# Driver.net
KiCad netlist of a schematic drawn in Altium Designer
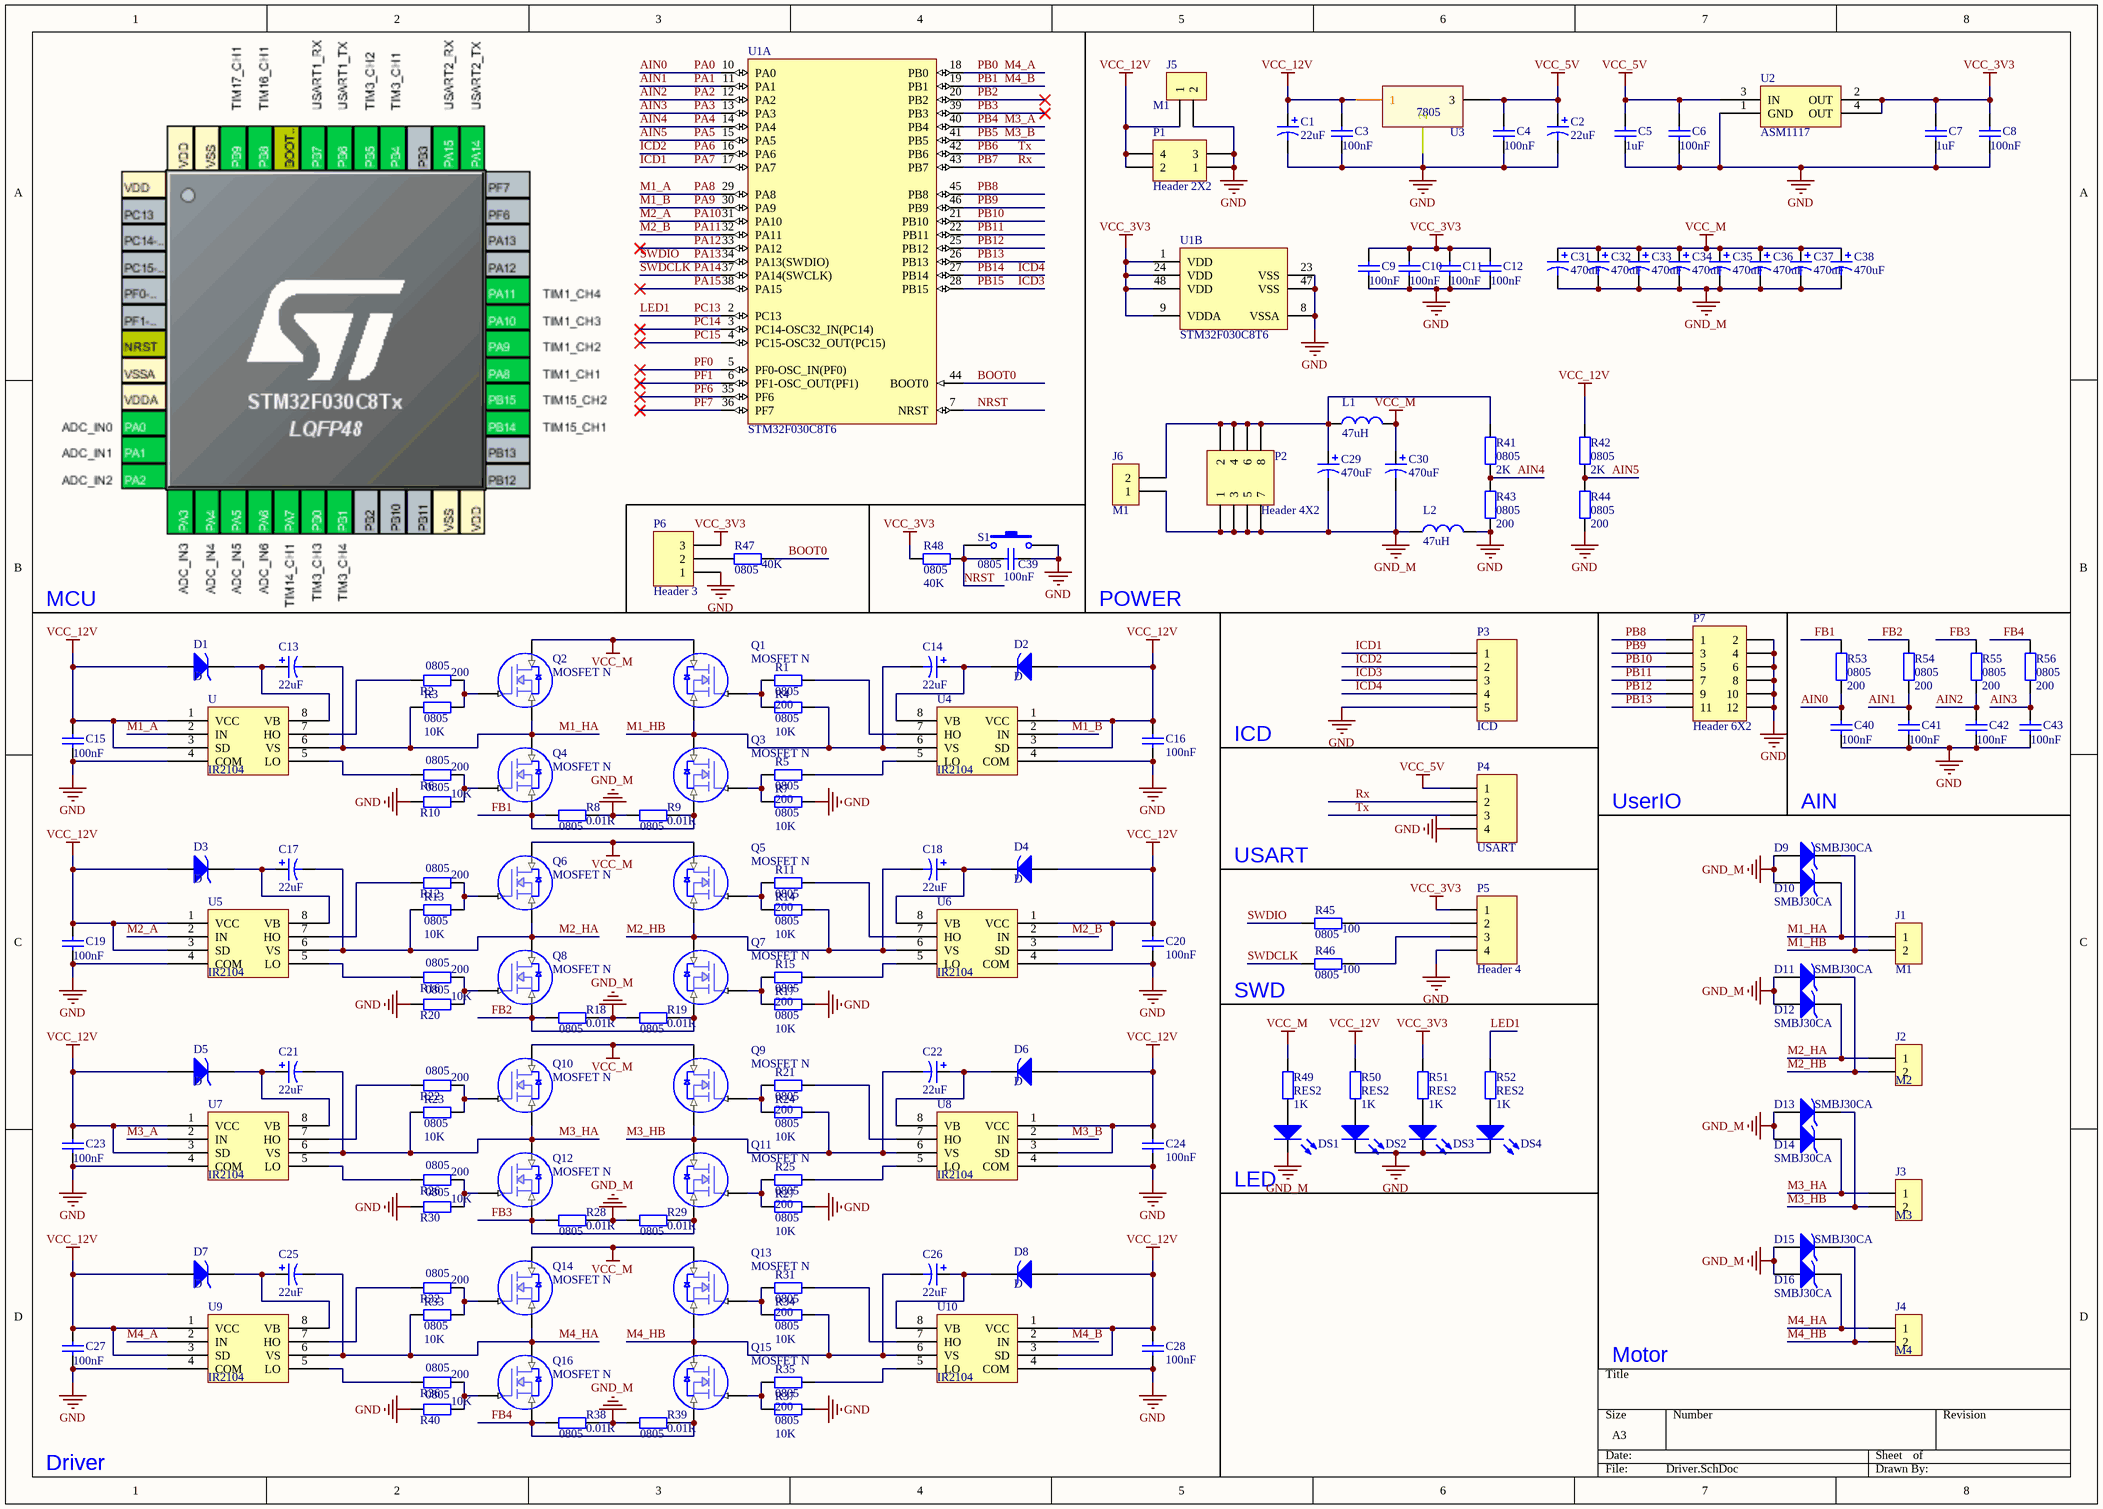
[diagram p0: Driver.SchDoc]

(export (version "E")
  (design (tool "Eeschema 10.0.6"))
  (components
    (comp (ref "C1")
      (value "22uF")
      (footprint "CD C(6032)")
      (fields (field (name "Comment") "CAP-ELEC"))
      (libsource (lib "QT") (part "CAP-ELEC"))
    )
    (comp (ref "C2")
      (value "22uF")
      (footprint "CD C(6032)")
      (fields (field (name "Comment") "CAP-ELEC"))
      (libsource (lib "QT") (part "CAP-ELEC"))
    )
    (comp (ref "C3")
      (value "100nF")
      (footprint "C 0805_L")
      (fields (field (name "Comment") "CAP"))
      (libsource (lib "QT") (part "CAP"))
    )
    (comp (ref "C4")
      (value "100nF")
      (footprint "C 0805_L")
      (fields (field (name "Comment") "CAP"))
      (libsource (lib "QT") (part "CAP"))
    )
    (comp (ref "C5")
      (value "1uF")
      (footprint "C 0805_L")
      (fields (field (name "Comment") "CAP"))
      (libsource (lib "QT") (part "CAP"))
    )
    (comp (ref "C6")
      (value "100nF")
      (footprint "C 0805_L")
      (fields (field (name "Comment") "CAP"))
      (libsource (lib "QT") (part "CAP"))
    )
    (comp (ref "C7")
      (value "1uF")
      (footprint "C 0805_L")
      (fields (field (name "Comment") "CAP"))
      (libsource (lib "QT") (part "CAP"))
    )
    (comp (ref "C8")
      (value "100nF")
      (footprint "C 0805_L")
      (fields (field (name "Comment") "CAP"))
      (libsource (lib "QT") (part "CAP"))
    )
    (comp (ref "C9")
      (value "100nF")
      (footprint "C 0805_L")
      (fields (field (name "Comment") "CAP"))
      (libsource (lib "QT") (part "CAP"))
    )
    (comp (ref "C10")
      (value "100nF")
      (footprint "C 0805_L")
      (fields (field (name "Comment") "CAP"))
      (libsource (lib "QT") (part "CAP"))
    )
    (comp (ref "C11")
      (value "100nF")
      (footprint "C 0805_L")
      (fields (field (name "Comment") "CAP"))
      (libsource (lib "QT") (part "CAP"))
    )
    (comp (ref "C12")
      (value "100nF")
      (footprint "C 0805_L")
      (fields (field (name "Comment") "CAP"))
      (libsource (lib "QT") (part "CAP"))
    )
    (comp (ref "C13")
      (value "22uF")
      (footprint "CD C(6032)")
      (fields (field (name "Comment") "CAP-ELEC"))
      (libsource (lib "QT") (part "CAP-ELEC"))
    )
    (comp (ref "C14")
      (value "22uF")
      (footprint "CD C(6032)")
      (fields (field (name "Comment") "CAP-ELEC"))
      (libsource (lib "") (part "CAP-ELEC_1"))
    )
    (comp (ref "C15")
      (value "100nF")
      (footprint "C 0805_L")
      (fields (field (name "Comment") "CAP"))
      (libsource (lib "QT") (part "CAP"))
    )
    (comp (ref "C16")
      (value "100nF")
      (footprint "C 0805_L")
      (fields (field (name "Comment") "CAP"))
      (libsource (lib "QT") (part "CAP"))
    )
    (comp (ref "C17")
      (value "22uF")
      (footprint "CD C(6032)")
      (fields (field (name "Comment") "CAP-ELEC"))
      (libsource (lib "QT") (part "CAP-ELEC"))
    )
    (comp (ref "C18")
      (value "22uF")
      (footprint "CD C(6032)")
      (fields (field (name "Comment") "CAP-ELEC"))
      (libsource (lib "") (part "CAP-ELEC_1"))
    )
    (comp (ref "C19")
      (value "100nF")
      (footprint "C 0805_L")
      (fields (field (name "Comment") "CAP"))
      (libsource (lib "QT") (part "CAP"))
    )
    (comp (ref "C20")
      (value "100nF")
      (footprint "C 0805_L")
      (fields (field (name "Comment") "CAP"))
      (libsource (lib "QT") (part "CAP"))
    )
    (comp (ref "C21")
      (value "22uF")
      (footprint "CD C(6032)")
      (fields (field (name "Comment") "CAP-ELEC"))
      (libsource (lib "QT") (part "CAP-ELEC"))
    )
    (comp (ref "C22")
      (value "22uF")
      (footprint "CD C(6032)")
      (fields (field (name "Comment") "CAP-ELEC"))
      (libsource (lib "") (part "CAP-ELEC_1"))
    )
    (comp (ref "C23")
      (value "100nF")
      (footprint "C 0805_L")
      (fields (field (name "Comment") "CAP"))
      (libsource (lib "QT") (part "CAP"))
    )
    (comp (ref "C24")
      (value "100nF")
      (footprint "C 0805_L")
      (fields (field (name "Comment") "CAP"))
      (libsource (lib "QT") (part "CAP"))
    )
    (comp (ref "C25")
      (value "22uF")
      (footprint "CD C(6032)")
      (fields (field (name "Comment") "CAP-ELEC"))
      (libsource (lib "QT") (part "CAP-ELEC"))
    )
    (comp (ref "C26")
      (value "22uF")
      (footprint "CD C(6032)")
      (fields (field (name "Comment") "CAP-ELEC"))
      (libsource (lib "") (part "CAP-ELEC_1"))
    )
    (comp (ref "C27")
      (value "100nF")
      (footprint "C 0805_L")
      (fields (field (name "Comment") "CAP"))
      (libsource (lib "QT") (part "CAP"))
    )
    (comp (ref "C28")
      (value "100nF")
      (footprint "C 0805_L")
      (fields (field (name "Comment") "CAP"))
      (libsource (lib "QT") (part "CAP"))
    )
    (comp (ref "C29")
      (value "470uF")
      (footprint "CM E(8*10.2)")
      (fields (field (name "Comment") "CAP-ELEC"))
      (libsource (lib "QT") (part "CAP-ELEC"))
    )
    (comp (ref "C30")
      (value "470uF")
      (footprint "CM E(8*10.2)")
      (fields (field (name "Comment") "CAP-ELEC"))
      (libsource (lib "QT") (part "CAP-ELEC"))
    )
    (comp (ref "C31")
      (value "470uF")
      (footprint "CM E(8*10.2)")
      (fields (field (name "Comment") "CAP-ELEC"))
      (libsource (lib "QT") (part "CAP-ELEC"))
    )
    (comp (ref "C32")
      (value "470uF")
      (footprint "CM E(8*10.2)")
      (fields (field (name "Comment") "CAP-ELEC"))
      (libsource (lib "QT") (part "CAP-ELEC"))
    )
    (comp (ref "C33")
      (value "470uF")
      (footprint "CM E(8*10.2)")
      (fields (field (name "Comment") "CAP-ELEC"))
      (libsource (lib "QT") (part "CAP-ELEC"))
    )
    (comp (ref "C34")
      (value "470uF")
      (footprint "CM E(8*10.2)")
      (fields (field (name "Comment") "CAP-ELEC"))
      (libsource (lib "QT") (part "CAP-ELEC"))
    )
    (comp (ref "C35")
      (value "470uF")
      (footprint "CM E(8*10.2)")
      (fields (field (name "Comment") "CAP-ELEC"))
      (libsource (lib "QT") (part "CAP-ELEC"))
    )
    (comp (ref "C36")
      (value "470uF")
      (footprint "CM E(8*10.2)")
      (fields (field (name "Comment") "CAP-ELEC"))
      (libsource (lib "QT") (part "CAP-ELEC"))
    )
    (comp (ref "C37")
      (value "470uF")
      (footprint "CM E(8*10.2)")
      (fields (field (name "Comment") "CAP-ELEC"))
      (libsource (lib "QT") (part "CAP-ELEC"))
    )
    (comp (ref "C38")
      (value "470uF")
      (footprint "CM E(8*10.2)")
      (fields (field (name "Comment") "CAP-ELEC"))
      (libsource (lib "QT") (part "CAP-ELEC"))
    )
    (comp (ref "C39")
      (value "0805")
      (footprint "C 0805_M")
      (fields (field (name "ALTIUM_VALUE") "100nF"))
      (libsource (lib "QT") (part "CAP"))
    )
    (comp (ref "C40")
      (value "100nF")
      (footprint "C 0805_L")
      (fields (field (name "Comment") "CAP"))
      (libsource (lib "QT") (part "CAP"))
    )
    (comp (ref "C41")
      (value "100nF")
      (footprint "C 0805_L")
      (fields (field (name "Comment") "CAP"))
      (libsource (lib "QT") (part "CAP"))
    )
    (comp (ref "C42")
      (value "100nF")
      (footprint "C 0805_L")
      (fields (field (name "Comment") "CAP"))
      (libsource (lib "QT") (part "CAP"))
    )
    (comp (ref "C43")
      (value "100nF")
      (footprint "C 0805_L")
      (fields (field (name "Comment") "CAP"))
      (libsource (lib "QT") (part "CAP"))
    )
    (comp (ref "D1")
      (value "D")
      (footprint "SOD-123")
      (description "High Conductance Fast Diode")
      (fields (field (name "PUBLISHER") "Altium Limited"))
      (libsource (lib "QT") (part "D"))
    )
    (comp (ref "D2")
      (value "D")
      (footprint "SOD-123")
      (description "High Conductance Fast Diode")
      (fields (field (name "PUBLISHER") "Altium Limited"))
      (libsource (lib "QT") (part "D"))
    )
    (comp (ref "D3")
      (value "D")
      (footprint "SOD-123")
      (description "High Conductance Fast Diode")
      (fields (field (name "PUBLISHER") "Altium Limited"))
      (libsource (lib "QT") (part "D"))
    )
    (comp (ref "D4")
      (value "D")
      (footprint "SOD-123")
      (description "High Conductance Fast Diode")
      (fields (field (name "PUBLISHER") "Altium Limited"))
      (libsource (lib "QT") (part "D"))
    )
    (comp (ref "D5")
      (value "D")
      (footprint "SOD-123")
      (description "High Conductance Fast Diode")
      (fields (field (name "PUBLISHER") "Altium Limited"))
      (libsource (lib "QT") (part "D"))
    )
    (comp (ref "D6")
      (value "D")
      (footprint "SOD-123")
      (description "High Conductance Fast Diode")
      (fields (field (name "PUBLISHER") "Altium Limited"))
      (libsource (lib "QT") (part "D"))
    )
    (comp (ref "D7")
      (value "D")
      (footprint "SOD-123")
      (description "High Conductance Fast Diode")
      (fields (field (name "PUBLISHER") "Altium Limited"))
      (libsource (lib "QT") (part "D"))
    )
    (comp (ref "D8")
      (value "D")
      (footprint "SOD-123")
      (description "High Conductance Fast Diode")
      (fields (field (name "PUBLISHER") "Altium Limited"))
      (libsource (lib "QT") (part "D"))
    )
    (comp (ref "D9")
      (value "SMBJ30CA")
      (footprint "SMB")
      (description "High Conductance Fast Diode")
      (fields (field (name "PUBLISHER") "Altium Limited"))
      (libsource (lib "QT") (part "D"))
    )
    (comp (ref "D10")
      (value "SMBJ30CA")
      (footprint "SMB")
      (description "High Conductance Fast Diode")
      (fields (field (name "PUBLISHER") "Altium Limited"))
      (libsource (lib "QT") (part "D"))
    )
    (comp (ref "D11")
      (value "SMBJ30CA")
      (footprint "SMB")
      (description "High Conductance Fast Diode")
      (fields (field (name "PUBLISHER") "Altium Limited"))
      (libsource (lib "QT") (part "D"))
    )
    (comp (ref "D12")
      (value "SMBJ30CA")
      (footprint "SMB")
      (description "High Conductance Fast Diode")
      (fields (field (name "PUBLISHER") "Altium Limited"))
      (libsource (lib "QT") (part "D"))
    )
    (comp (ref "D13")
      (value "SMBJ30CA")
      (footprint "SMB")
      (description "High Conductance Fast Diode")
      (fields (field (name "PUBLISHER") "Altium Limited"))
      (libsource (lib "QT") (part "D"))
    )
    (comp (ref "D14")
      (value "SMBJ30CA")
      (footprint "SMB")
      (description "High Conductance Fast Diode")
      (fields (field (name "PUBLISHER") "Altium Limited"))
      (libsource (lib "QT") (part "D"))
    )
    (comp (ref "D15")
      (value "SMBJ30CA")
      (footprint "SMB")
      (description "High Conductance Fast Diode")
      (fields (field (name "PUBLISHER") "Altium Limited"))
      (libsource (lib "QT") (part "D"))
    )
    (comp (ref "D16")
      (value "SMBJ30CA")
      (footprint "SMB")
      (description "High Conductance Fast Diode")
      (fields (field (name "PUBLISHER") "Altium Limited"))
      (libsource (lib "QT") (part "D"))
    )
    (comp (ref "DS1") (value "LED") (footprint "LED 0805B") (libsource (lib "QT") (part "LED")))
    (comp (ref "DS2") (value "LED") (footprint "LED 0805B") (libsource (lib "QT") (part "LED")))
    (comp (ref "DS3") (value "LED") (footprint "LED 0805B") (libsource (lib "QT") (part "LED")))
    (comp (ref "DS4") (value "LED") (footprint "LED 0805B") (libsource (lib "QT") (part "LED")))
    (comp (ref "J1") (value "M1") (footprint "DG1282-5.0") (libsource (lib "") (part "CON2_1")))
    (comp (ref "J2") (value "M2") (footprint "DG1282-5.0") (libsource (lib "") (part "CON2_1")))
    (comp (ref "J3") (value "M3") (footprint "DG1282-5.0") (libsource (lib "") (part "CON2_1")))
    (comp (ref "J4") (value "M4") (footprint "DG1282-5.0") (libsource (lib "") (part "CON2_1")))
    (comp (ref "J5") (value "M1") (footprint "DG1282-5.0") (libsource (lib "常用元件库") (part "CON2")))
    (comp (ref "J6") (value "M1") (footprint "DG1282-5.0") (libsource (lib "") (part "CON2_2")))
    (comp (ref "L1")
      (value "47uH")
      (footprint "L-SMD-12")
      (description "电感")
      (fields (field (name "Comment") "Inductor") (field (name "PUBLISHER") "Altium Limited"))
      (libsource (lib "Fszhang") (part "Inductor"))
    )
    (comp (ref "L2")
      (value "47uH")
      (footprint "L-SMD-12")
      (description "电感")
      (fields (field (name "Comment") "Inductor") (field (name "PUBLISHER") "Altium Limited"))
      (libsource (lib "Fszhang") (part "Inductor"))
    )
    (comp (ref "P1")
      (value "Header 2X2")
      (footprint "HDR2.54-LI-2x2P")
      (description "Header, 2-Pin, Dual row")
      (fields (field (name "PUBLISHER") "Altium Limited"))
      (libsource (lib "QT") (part "Header 2X2"))
    )
    (comp (ref "P2")
      (value "Header 4X2")
      (footprint "HDR2.54-LI-2x4P")
      (description "Header, 4-Pin, Dual row")
      (fields (field (name "PUBLISHER") "Altium Limited"))
      (libsource (lib "QT") (part "Header 4X2"))
    )
    (comp (ref "P3")
      (value "ICD")
      (footprint "HDR2.54-LI-5P")
      (description "Header, 5-Pin")
      (fields (field (name "PUBLISHER") "Altium Limited"))
      (libsource (lib "QT") (part "Header 5"))
    )
    (comp (ref "P4")
      (value "USART")
      (footprint "HDR2.54-LI-4P")
      (description "Header, 4-Pin")
      (fields (field (name "PUBLISHER") "Altium Limited"))
      (libsource (lib "QT") (part "Header 4"))
    )
    (comp (ref "P5")
      (value "Header 4")
      (footprint "HDR2.54-LI-4P")
      (description "Header, 4-Pin")
      (fields (field (name "PUBLISHER") "Altium Limited"))
      (libsource (lib "QT") (part "Header 4"))
    )
    (comp (ref "P6")
      (value "Header 3")
      (footprint "HDR2.54-LI-3P")
      (description "Header, 3-Pin")
      (fields (field (name "PUBLISHER") "Altium Limited"))
      (libsource (lib "QT") (part "Header 3"))
    )
    (comp (ref "P7")
      (value "Header 6X2")
      (footprint "HDR2.54-LI-2x6P")
      (description "Header, 6-Pin, Dual row")
      (fields (field (name "PUBLISHER") "Altium Limited"))
      (libsource (lib "QT") (part "Header 6X2"))
    )
    (comp (ref "Q1") (value "MOSFET N") (footprint "TO252") (libsource (lib "场效应管及可控硅") (part "MOSFET N")))
    (comp (ref "Q2") (value "MOSFET N") (footprint "TO252") (libsource (lib "场效应管及可控硅") (part "MOSFET N")))
    (comp (ref "Q3") (value "MOSFET N") (footprint "TO252") (libsource (lib "场效应管及可控硅") (part "MOSFET N")))
    (comp (ref "Q4") (value "MOSFET N") (footprint "TO252") (libsource (lib "场效应管及可控硅") (part "MOSFET N")))
    (comp (ref "Q5") (value "MOSFET N") (footprint "TO252") (libsource (lib "场效应管及可控硅") (part "MOSFET N")))
    (comp (ref "Q6") (value "MOSFET N") (footprint "TO252") (libsource (lib "场效应管及可控硅") (part "MOSFET N")))
    (comp (ref "Q7") (value "MOSFET N") (footprint "TO252") (libsource (lib "场效应管及可控硅") (part "MOSFET N")))
    (comp (ref "Q8") (value "MOSFET N") (footprint "TO252") (libsource (lib "场效应管及可控硅") (part "MOSFET N")))
    (comp (ref "Q9") (value "MOSFET N") (footprint "TO252") (libsource (lib "场效应管及可控硅") (part "MOSFET N")))
    (comp (ref "Q10") (value "MOSFET N") (footprint "TO252") (libsource (lib "场效应管及可控硅") (part "MOSFET N")))
    (comp (ref "Q11") (value "MOSFET N") (footprint "TO252") (libsource (lib "场效应管及可控硅") (part "MOSFET N")))
    (comp (ref "Q12") (value "MOSFET N") (footprint "TO252") (libsource (lib "场效应管及可控硅") (part "MOSFET N")))
    (comp (ref "Q13") (value "MOSFET N") (footprint "TO252") (libsource (lib "场效应管及可控硅") (part "MOSFET N")))
    (comp (ref "Q14") (value "MOSFET N") (footprint "TO252") (libsource (lib "场效应管及可控硅") (part "MOSFET N")))
    (comp (ref "Q15") (value "MOSFET N") (footprint "TO252") (libsource (lib "场效应管及可控硅") (part "MOSFET N")))
    (comp (ref "Q16") (value "MOSFET N") (footprint "TO252") (libsource (lib "场效应管及可控硅") (part "MOSFET N")))
    (comp (ref "R1")
      (value "0805")
      (footprint "R 0805_L")
      (description "Resistor")
      (fields (field (name "ALTIUM_VALUE") "200") (field (name "PUBLISHER") "Altium Limited"))
      (libsource (lib "") (part "RES2_1"))
    )
    (comp (ref "R2")
      (value "0805")
      (footprint "R 0805_L")
      (description "Resistor")
      (fields (field (name "ALTIUM_VALUE") "200") (field (name "PUBLISHER") "Altium Limited"))
      (libsource (lib "") (part "RES2_3"))
    )
    (comp (ref "R3")
      (value "0805")
      (footprint "R 0805_L")
      (description "Resistor")
      (fields (field (name "ALTIUM_VALUE") "10K") (field (name "PUBLISHER") "Altium Limited"))
      (libsource (lib "QT") (part "RES2"))
    )
    (comp (ref "R4")
      (value "0805")
      (footprint "R 0805_L")
      (description "Resistor")
      (fields (field (name "ALTIUM_VALUE") "10K") (field (name "PUBLISHER") "Altium Limited"))
      (libsource (lib "") (part "RES2_2"))
    )
    (comp (ref "R5")
      (value "0805")
      (footprint "R 0805_L")
      (description "Resistor")
      (fields (field (name "ALTIUM_VALUE") "200") (field (name "PUBLISHER") "Altium Limited"))
      (libsource (lib "") (part "RES2_1"))
    )
    (comp (ref "R6")
      (value "0805")
      (footprint "R 0805_L")
      (description "Resistor")
      (fields (field (name "ALTIUM_VALUE") "200") (field (name "PUBLISHER") "Altium Limited"))
      (libsource (lib "") (part "RES2_3"))
    )
    (comp (ref "R7")
      (value "0805")
      (footprint "R 0805_L")
      (description "Resistor")
      (fields (field (name "ALTIUM_VALUE") "10K") (field (name "PUBLISHER") "Altium Limited"))
      (libsource (lib "") (part "RES2_1"))
    )
    (comp (ref "R8")
      (value "0805")
      (footprint "R 1206_L")
      (description "Resistor")
      (fields (field (name "ALTIUM_VALUE") "0.01R") (field (name "PUBLISHER") "Altium Limited"))
      (libsource (lib "") (part "RES2_3"))
    )
    (comp (ref "R9")
      (value "0805")
      (footprint "R 1206_L")
      (description "Resistor")
      (fields (field (name "ALTIUM_VALUE") "0.01R") (field (name "PUBLISHER") "Altium Limited"))
      (libsource (lib "") (part "RES2_3"))
    )
    (comp (ref "R10")
      (value "0805")
      (footprint "R 0805_L")
      (description "Resistor")
      (fields (field (name "ALTIUM_VALUE") "10K") (field (name "PUBLISHER") "Altium Limited"))
      (libsource (lib "") (part "RES2_3"))
    )
    (comp (ref "R11")
      (value "0805")
      (footprint "R 0805_L")
      (description "Resistor")
      (fields (field (name "ALTIUM_VALUE") "200") (field (name "PUBLISHER") "Altium Limited"))
      (libsource (lib "") (part "RES2_1"))
    )
    (comp (ref "R12")
      (value "0805")
      (footprint "R 0805_L")
      (description "Resistor")
      (fields (field (name "ALTIUM_VALUE") "200") (field (name "PUBLISHER") "Altium Limited"))
      (libsource (lib "") (part "RES2_3"))
    )
    (comp (ref "R13")
      (value "0805")
      (footprint "R 0805_L")
      (description "Resistor")
      (fields (field (name "ALTIUM_VALUE") "10K") (field (name "PUBLISHER") "Altium Limited"))
      (libsource (lib "QT") (part "RES2"))
    )
    (comp (ref "R14")
      (value "0805")
      (footprint "R 0805_L")
      (description "Resistor")
      (fields (field (name "ALTIUM_VALUE") "10K") (field (name "PUBLISHER") "Altium Limited"))
      (libsource (lib "") (part "RES2_2"))
    )
    (comp (ref "R15")
      (value "0805")
      (footprint "R 0805_L")
      (description "Resistor")
      (fields (field (name "ALTIUM_VALUE") "200") (field (name "PUBLISHER") "Altium Limited"))
      (libsource (lib "") (part "RES2_1"))
    )
    (comp (ref "R16")
      (value "0805")
      (footprint "R 0805_L")
      (description "Resistor")
      (fields (field (name "ALTIUM_VALUE") "200") (field (name "PUBLISHER") "Altium Limited"))
      (libsource (lib "") (part "RES2_3"))
    )
    (comp (ref "R17")
      (value "0805")
      (footprint "R 0805_L")
      (description "Resistor")
      (fields (field (name "ALTIUM_VALUE") "10K") (field (name "PUBLISHER") "Altium Limited"))
      (libsource (lib "") (part "RES2_1"))
    )
    (comp (ref "R18")
      (value "0805")
      (footprint "R 1206_L")
      (description "Resistor")
      (fields (field (name "ALTIUM_VALUE") "0.01R") (field (name "PUBLISHER") "Altium Limited"))
      (libsource (lib "") (part "RES2_3"))
    )
    (comp (ref "R19")
      (value "0805")
      (footprint "R 1206_L")
      (description "Resistor")
      (fields (field (name "ALTIUM_VALUE") "0.01R") (field (name "PUBLISHER") "Altium Limited"))
      (libsource (lib "") (part "RES2_3"))
    )
    (comp (ref "R20")
      (value "0805")
      (footprint "R 0805_L")
      (description "Resistor")
      (fields (field (name "ALTIUM_VALUE") "10K") (field (name "PUBLISHER") "Altium Limited"))
      (libsource (lib "") (part "RES2_3"))
    )
    (comp (ref "R21")
      (value "0805")
      (footprint "R 0805_L")
      (description "Resistor")
      (fields (field (name "ALTIUM_VALUE") "200") (field (name "PUBLISHER") "Altium Limited"))
      (libsource (lib "") (part "RES2_1"))
    )
    (comp (ref "R22")
      (value "0805")
      (footprint "R 0805_L")
      (description "Resistor")
      (fields (field (name "ALTIUM_VALUE") "200") (field (name "PUBLISHER") "Altium Limited"))
      (libsource (lib "") (part "RES2_3"))
    )
    (comp (ref "R23")
      (value "0805")
      (footprint "R 0805_L")
      (description "Resistor")
      (fields (field (name "ALTIUM_VALUE") "10K") (field (name "PUBLISHER") "Altium Limited"))
      (libsource (lib "QT") (part "RES2"))
    )
    (comp (ref "R24")
      (value "0805")
      (footprint "R 0805_L")
      (description "Resistor")
      (fields (field (name "ALTIUM_VALUE") "10K") (field (name "PUBLISHER") "Altium Limited"))
      (libsource (lib "") (part "RES2_2"))
    )
    (comp (ref "R25")
      (value "0805")
      (footprint "R 0805_L")
      (description "Resistor")
      (fields (field (name "ALTIUM_VALUE") "200") (field (name "PUBLISHER") "Altium Limited"))
      (libsource (lib "") (part "RES2_1"))
    )
    (comp (ref "R26")
      (value "0805")
      (footprint "R 0805_L")
      (description "Resistor")
      (fields (field (name "ALTIUM_VALUE") "200") (field (name "PUBLISHER") "Altium Limited"))
      (libsource (lib "") (part "RES2_3"))
    )
    (comp (ref "R27")
      (value "0805")
      (footprint "R 0805_L")
      (description "Resistor")
      (fields (field (name "ALTIUM_VALUE") "10K") (field (name "PUBLISHER") "Altium Limited"))
      (libsource (lib "") (part "RES2_1"))
    )
    (comp (ref "R28")
      (value "0805")
      (footprint "R 1206_L")
      (description "Resistor")
      (fields (field (name "ALTIUM_VALUE") "0.01R") (field (name "PUBLISHER") "Altium Limited"))
      (libsource (lib "") (part "RES2_3"))
    )
    (comp (ref "R29")
      (value "0805")
      (footprint "R 1206_L")
      (description "Resistor")
      (fields (field (name "ALTIUM_VALUE") "0.01R") (field (name "PUBLISHER") "Altium Limited"))
      (libsource (lib "") (part "RES2_3"))
    )
    (comp (ref "R30")
      (value "0805")
      (footprint "R 0805_L")
      (description "Resistor")
      (fields (field (name "ALTIUM_VALUE") "10K") (field (name "PUBLISHER") "Altium Limited"))
      (libsource (lib "") (part "RES2_3"))
    )
    (comp (ref "R31")
      (value "0805")
      (footprint "R 0805_L")
      (description "Resistor")
      (fields (field (name "ALTIUM_VALUE") "200") (field (name "PUBLISHER") "Altium Limited"))
      (libsource (lib "") (part "RES2_1"))
    )
    (comp (ref "R32")
      (value "0805")
      (footprint "R 0805_L")
      (description "Resistor")
      (fields (field (name "ALTIUM_VALUE") "200") (field (name "PUBLISHER") "Altium Limited"))
      (libsource (lib "") (part "RES2_3"))
    )
    (comp (ref "R33")
      (value "0805")
      (footprint "R 0805_L")
      (description "Resistor")
      (fields (field (name "ALTIUM_VALUE") "10K") (field (name "PUBLISHER") "Altium Limited"))
      (libsource (lib "QT") (part "RES2"))
    )
    (comp (ref "R34")
      (value "0805")
      (footprint "R 0805_L")
      (description "Resistor")
      (fields (field (name "ALTIUM_VALUE") "10K") (field (name "PUBLISHER") "Altium Limited"))
      (libsource (lib "") (part "RES2_2"))
    )
    (comp (ref "R35")
      (value "0805")
      (footprint "R 0805_L")
      (description "Resistor")
      (fields (field (name "ALTIUM_VALUE") "200") (field (name "PUBLISHER") "Altium Limited"))
      (libsource (lib "") (part "RES2_1"))
    )
    (comp (ref "R36")
      (value "0805")
      (footprint "R 0805_L")
      (description "Resistor")
      (fields (field (name "ALTIUM_VALUE") "200") (field (name "PUBLISHER") "Altium Limited"))
      (libsource (lib "") (part "RES2_3"))
    )
    (comp (ref "R37")
      (value "0805")
      (footprint "R 0805_L")
      (description "Resistor")
      (fields (field (name "ALTIUM_VALUE") "10K") (field (name "PUBLISHER") "Altium Limited"))
      (libsource (lib "") (part "RES2_1"))
    )
    (comp (ref "R38")
      (value "0805")
      (footprint "R 1206_L")
      (description "Resistor")
      (fields (field (name "ALTIUM_VALUE") "0.01R") (field (name "PUBLISHER") "Altium Limited"))
      (libsource (lib "") (part "RES2_3"))
    )
    (comp (ref "R39")
      (value "0805")
      (footprint "R 1206_L")
      (description "Resistor")
      (fields (field (name "ALTIUM_VALUE") "0.01R") (field (name "PUBLISHER") "Altium Limited"))
      (libsource (lib "") (part "RES2_3"))
    )
    (comp (ref "R40")
      (value "0805")
      (footprint "R 0805_L")
      (description "Resistor")
      (fields (field (name "ALTIUM_VALUE") "10K") (field (name "PUBLISHER") "Altium Limited"))
      (libsource (lib "") (part "RES2_3"))
    )
    (comp (ref "R41")
      (value "0805")
      (footprint "R 0805_L")
      (description "Resistor")
      (fields (field (name "ALTIUM_VALUE") "2K") (field (name "PUBLISHER") "Altium Limited"))
      (libsource (lib "QT") (part "RES2"))
    )
    (comp (ref "R42")
      (value "0805")
      (footprint "R 0805_L")
      (description "Resistor")
      (fields (field (name "ALTIUM_VALUE") "2K") (field (name "PUBLISHER") "Altium Limited"))
      (libsource (lib "QT") (part "RES2"))
    )
    (comp (ref "R43")
      (value "0805")
      (footprint "R 0805_L")
      (description "Resistor")
      (fields (field (name "ALTIUM_VALUE") "200") (field (name "PUBLISHER") "Altium Limited"))
      (libsource (lib "QT") (part "RES2"))
    )
    (comp (ref "R44")
      (value "0805")
      (footprint "R 0805_L")
      (description "Resistor")
      (fields (field (name "ALTIUM_VALUE") "200") (field (name "PUBLISHER") "Altium Limited"))
      (libsource (lib "QT") (part "RES2"))
    )
    (comp (ref "R45")
      (value "0805")
      (footprint "R 0805_L")
      (description "Resistor")
      (fields (field (name "ALTIUM_VALUE") "100") (field (name "PUBLISHER") "Altium Limited"))
      (libsource (lib "") (part "RES2_3"))
    )
    (comp (ref "R46")
      (value "0805")
      (footprint "R 0805_L")
      (description "Resistor")
      (fields (field (name "ALTIUM_VALUE") "100") (field (name "PUBLISHER") "Altium Limited"))
      (libsource (lib "") (part "RES2_3"))
    )
    (comp (ref "R47")
      (value "0805")
      (footprint "R 0805_L")
      (description "Resistor")
      (fields (field (name "ALTIUM_VALUE") "40K") (field (name "PUBLISHER") "Altium Limited"))
      (libsource (lib "") (part "RES2_3"))
    )
    (comp (ref "R48")
      (value "0805")
      (footprint "R 0805_L")
      (description "Resistor")
      (fields (field (name "ALTIUM_VALUE") "40K") (field (name "PUBLISHER") "Altium Limited"))
      (libsource (lib "") (part "RES2_3"))
    )
    (comp (ref "R49")
      (value "RES2")
      (footprint "R 0805_L")
      (description "Resistor")
      (fields (field (name "ALTIUM_VALUE") "1K") (field (name "PUBLISHER") "Altium Limited"))
      (libsource (lib "") (part "RES2_2"))
    )
    (comp (ref "R50")
      (value "RES2")
      (footprint "R 0805_L")
      (description "Resistor")
      (fields (field (name "ALTIUM_VALUE") "1K") (field (name "PUBLISHER") "Altium Limited"))
      (libsource (lib "") (part "RES2_2"))
    )
    (comp (ref "R51")
      (value "RES2")
      (footprint "R 0805_L")
      (description "Resistor")
      (fields (field (name "ALTIUM_VALUE") "1K") (field (name "PUBLISHER") "Altium Limited"))
      (libsource (lib "") (part "RES2_2"))
    )
    (comp (ref "R52")
      (value "RES2")
      (footprint "R 0805_L")
      (description "Resistor")
      (fields (field (name "ALTIUM_VALUE") "1K") (field (name "PUBLISHER") "Altium Limited"))
      (libsource (lib "") (part "RES2_2"))
    )
    (comp (ref "R53")
      (value "0805")
      (footprint "R 0805_L")
      (description "Resistor")
      (fields (field (name "ALTIUM_VALUE") "200") (field (name "PUBLISHER") "Altium Limited"))
      (libsource (lib "") (part "RES2_3"))
    )
    (comp (ref "R54")
      (value "0805")
      (footprint "R 0805_L")
      (description "Resistor")
      (fields (field (name "ALTIUM_VALUE") "200") (field (name "PUBLISHER") "Altium Limited"))
      (libsource (lib "") (part "RES2_3"))
    )
    (comp (ref "R55")
      (value "0805")
      (footprint "R 0805_L")
      (description "Resistor")
      (fields (field (name "ALTIUM_VALUE") "200") (field (name "PUBLISHER") "Altium Limited"))
      (libsource (lib "") (part "RES2_3"))
    )
    (comp (ref "R56")
      (value "0805")
      (footprint "R 0805_L")
      (description "Resistor")
      (fields (field (name "ALTIUM_VALUE") "200") (field (name "PUBLISHER") "Altium Limited"))
      (libsource (lib "") (part "RES2_3"))
    )
    (comp (ref "S1")
      (value "SW")
      (footprint "TSW DIP-3*6*4.3")
      (fields (field (name "PUBLISHER") "Altium Limited"))
      (libsource (lib "QT") (part "SW"))
    )
    (comp (ref "U") (value "IR2104") (footprint "SOP8_M") (libsource (lib "") (part "IR2104_1")))
    (comp (ref "U1")
      (value "STM32F030C8T6")
      (footprint "STM-LQFP48_N")
      (libsource (lib "STMicroelectronics STM32 F0") (part "STM32F030C8T6"))
    )
    (comp (ref "U2")
      (value "ASM1117")
      (footprint "SOT-223")
      (description "3.3V稳压芯片")
      (libsource (lib "Fszhang") (part "ASM1117"))
    )
    (comp (ref "U3") (value "7805") (footprint "TO220B") (libsource (lib "QT") (part "7805")))
    (comp (ref "U4") (value "IR2104") (footprint "SOP8_M") (libsource (lib "常用元件库") (part "IR2104")))
    (comp (ref "U5") (value "IR2104") (footprint "SOP8_M") (libsource (lib "") (part "IR2104_1")))
    (comp (ref "U6") (value "IR2104") (footprint "SOP8_M") (libsource (lib "常用元件库") (part "IR2104")))
    (comp (ref "U7") (value "IR2104") (footprint "SOP8_M") (libsource (lib "") (part "IR2104_1")))
    (comp (ref "U8") (value "IR2104") (footprint "SOP8_M") (libsource (lib "常用元件库") (part "IR2104")))
    (comp (ref "U9") (value "IR2104") (footprint "SOP8_M") (libsource (lib "") (part "IR2104_1")))
    (comp (ref "U10") (value "IR2104") (footprint "SOP8_M") (libsource (lib "常用元件库") (part "IR2104")))
  )
  (nets
    (net (code "1") (name "/AIN0") (class "Default")
      (node (ref "C40") (pin "1") (pinfunction "1_1") (pintype "passive"))
      (node (ref "R53") (pin "1") (pinfunction "1_1") (pintype "passive"))
      (node (ref "U1") (pin "10") (pinfunction "PA0_10") (pintype "bidirectional"))
    )
    (net (code "2") (name "/AIN1") (class "Default")
      (node (ref "C41") (pin "1") (pinfunction "1_1") (pintype "passive"))
      (node (ref "R54") (pin "1") (pinfunction "1_1") (pintype "passive"))
      (node (ref "U1") (pin "11") (pinfunction "PA1_11") (pintype "bidirectional"))
    )
    (net (code "3") (name "/AIN2") (class "Default")
      (node (ref "C42") (pin "1") (pinfunction "1_1") (pintype "passive"))
      (node (ref "R55") (pin "1") (pinfunction "1_1") (pintype "passive"))
      (node (ref "U1") (pin "12") (pinfunction "PA2_12") (pintype "bidirectional"))
    )
    (net (code "4") (name "/AIN3") (class "Default")
      (node (ref "C43") (pin "1") (pinfunction "1_1") (pintype "passive"))
      (node (ref "R56") (pin "1") (pinfunction "1_1") (pintype "passive"))
      (node (ref "U1") (pin "13") (pinfunction "PA3_13") (pintype "bidirectional"))
    )
    (net (code "5") (name "/AIN4") (class "Default")
      (node (ref "R41") (pin "2") (pinfunction "2_2") (pintype "passive"))
      (node (ref "R43") (pin "1") (pinfunction "1_1") (pintype "passive"))
      (node (ref "U1") (pin "14") (pinfunction "PA4_14") (pintype "bidirectional"))
    )
    (net (code "6") (name "/AIN5") (class "Default")
      (node (ref "R42") (pin "2") (pinfunction "2_2") (pintype "passive"))
      (node (ref "R44") (pin "1") (pinfunction "1_1") (pintype "passive"))
      (node (ref "U1") (pin "15") (pinfunction "PA5_15") (pintype "bidirectional"))
    )
    (net (code "7") (name "/BOOT0") (class "Default")
      (node (ref "R47") (pin "2") (pinfunction "2_2") (pintype "passive"))
      (node (ref "U1") (pin "44") (pinfunction "BOOT0_44") (pintype "input"))
    )
    (net (code "8") (name "/FB1") (class "Default")
      (node (ref "Q3") (pin "3") (pinfunction "S_3") (pintype "input"))
      (node (ref "Q4") (pin "3") (pinfunction "S_3") (pintype "input"))
      (node (ref "R53") (pin "2") (pinfunction "2_2") (pintype "passive"))
      (node (ref "R8") (pin "1") (pinfunction "1_1") (pintype "passive"))
      (node (ref "R9") (pin "2") (pinfunction "2_2") (pintype "passive"))
    )
    (net (code "9") (name "/FB2") (class "Default")
      (node (ref "Q7") (pin "3") (pinfunction "S_3") (pintype "input"))
      (node (ref "Q8") (pin "3") (pinfunction "S_3") (pintype "input"))
      (node (ref "R18") (pin "1") (pinfunction "1_1") (pintype "passive"))
      (node (ref "R19") (pin "2") (pinfunction "2_2") (pintype "passive"))
      (node (ref "R54") (pin "2") (pinfunction "2_2") (pintype "passive"))
    )
    (net (code "10") (name "/FB3") (class "Default")
      (node (ref "Q11") (pin "3") (pinfunction "S_3") (pintype "input"))
      (node (ref "Q12") (pin "3") (pinfunction "S_3") (pintype "input"))
      (node (ref "R28") (pin "1") (pinfunction "1_1") (pintype "passive"))
      (node (ref "R29") (pin "2") (pinfunction "2_2") (pintype "passive"))
      (node (ref "R55") (pin "2") (pinfunction "2_2") (pintype "passive"))
    )
    (net (code "11") (name "/FB4") (class "Default")
      (node (ref "Q15") (pin "3") (pinfunction "S_3") (pintype "input"))
      (node (ref "Q16") (pin "3") (pinfunction "S_3") (pintype "input"))
      (node (ref "R38") (pin "1") (pinfunction "1_1") (pintype "passive"))
      (node (ref "R39") (pin "2") (pinfunction "2_2") (pintype "passive"))
      (node (ref "R56") (pin "2") (pinfunction "2_2") (pintype "passive"))
    )
    (net (code "12") (name "/ICD1") (class "Default")
      (node (ref "P3") (pin "1") (pinfunction "1_1") (pintype "passive"))
      (node (ref "U1") (pin "17") (pinfunction "PA7_17") (pintype "bidirectional"))
    )
    (net (code "13") (name "/ICD2") (class "Default")
      (node (ref "P3") (pin "2") (pinfunction "2_2") (pintype "passive"))
      (node (ref "U1") (pin "16") (pinfunction "PA6_16") (pintype "bidirectional"))
    )
    (net (code "14") (name "/ICD3") (class "Default")
      (node (ref "P3") (pin "3") (pinfunction "3_3") (pintype "passive"))
      (node (ref "U1") (pin "28") (pinfunction "PB15_28") (pintype "bidirectional"))
    )
    (net (code "15") (name "/ICD4") (class "Default")
      (node (ref "P3") (pin "4") (pinfunction "4_4") (pintype "passive"))
      (node (ref "U1") (pin "27") (pinfunction "PB14_27") (pintype "bidirectional"))
    )
    (net (code "16") (name "/LED1") (class "Default")
      (node (ref "R52") (pin "2") (pinfunction "2_2") (pintype "passive"))
      (node (ref "U1") (pin "2") (pinfunction "PC13_2") (pintype "bidirectional"))
    )
    (net (code "17") (name "/M1_A") (class "Default")
      (node (ref "U") (pin "2") (pinfunction "IN_2") (pintype "passive"))
      (node (ref "U1") (pin "29") (pinfunction "PA8_29") (pintype "bidirectional"))
    )
    (net (code "18") (name "/M1_B") (class "Default")
      (node (ref "U1") (pin "30") (pinfunction "PA9_30") (pintype "bidirectional"))
      (node (ref "U4") (pin "2") (pinfunction "IN_2") (pintype "passive"))
    )
    (net (code "19") (name "/M1_HA") (class "Default")
      (node (ref "C13") (pin "2") (pinfunction "2_2") (pintype "passive"))
      (node (ref "D10") (pin "2") (pinfunction "K_2") (pintype "passive"))
      (node (ref "J1") (pin "1") (pinfunction "1_1") (pintype "passive"))
      (node (ref "Q2") (pin "3") (pinfunction "S_3") (pintype "input"))
      (node (ref "Q4") (pin "2") (pinfunction "D_2") (pintype "input"))
      (node (ref "R3") (pin "2") (pinfunction "2_2") (pintype "passive"))
      (node (ref "U") (pin "6") (pinfunction "VS_6") (pintype "passive"))
    )
    (net (code "20") (name "/M1_HB") (class "Default")
      (node (ref "C14") (pin "2") (pinfunction "2_2") (pintype "passive"))
      (node (ref "D9") (pin "2") (pinfunction "K_2") (pintype "passive"))
      (node (ref "J1") (pin "2") (pinfunction "2_2") (pintype "passive"))
      (node (ref "Q1") (pin "3") (pinfunction "S_3") (pintype "input"))
      (node (ref "Q3") (pin "2") (pinfunction "D_2") (pintype "input"))
      (node (ref "R4") (pin "2") (pinfunction "2_2") (pintype "passive"))
      (node (ref "U4") (pin "6") (pinfunction "VS_6") (pintype "passive"))
    )
    (net (code "21") (name "/M2_A") (class "Default")
      (node (ref "U1") (pin "31") (pinfunction "PA10_31") (pintype "bidirectional"))
      (node (ref "U5") (pin "2") (pinfunction "IN_2") (pintype "passive"))
    )
    (net (code "22") (name "/M2_B") (class "Default")
      (node (ref "U1") (pin "32") (pinfunction "PA11_32") (pintype "bidirectional"))
      (node (ref "U6") (pin "2") (pinfunction "IN_2") (pintype "passive"))
    )
    (net (code "23") (name "/M2_HA") (class "Default")
      (node (ref "C17") (pin "2") (pinfunction "2_2") (pintype "passive"))
      (node (ref "D12") (pin "2") (pinfunction "K_2") (pintype "passive"))
      (node (ref "J2") (pin "1") (pinfunction "1_1") (pintype "passive"))
      (node (ref "Q6") (pin "3") (pinfunction "S_3") (pintype "input"))
      (node (ref "Q8") (pin "2") (pinfunction "D_2") (pintype "input"))
      (node (ref "R13") (pin "2") (pinfunction "2_2") (pintype "passive"))
      (node (ref "U5") (pin "6") (pinfunction "VS_6") (pintype "passive"))
    )
    (net (code "24") (name "/M2_HB") (class "Default")
      (node (ref "C18") (pin "2") (pinfunction "2_2") (pintype "passive"))
      (node (ref "D11") (pin "2") (pinfunction "K_2") (pintype "passive"))
      (node (ref "J2") (pin "2") (pinfunction "2_2") (pintype "passive"))
      (node (ref "Q5") (pin "3") (pinfunction "S_3") (pintype "input"))
      (node (ref "Q7") (pin "2") (pinfunction "D_2") (pintype "input"))
      (node (ref "R14") (pin "2") (pinfunction "2_2") (pintype "passive"))
      (node (ref "U6") (pin "6") (pinfunction "VS_6") (pintype "passive"))
    )
    (net (code "25") (name "/M3_A") (class "Default")
      (node (ref "U1") (pin "40") (pinfunction "PB4_40") (pintype "bidirectional"))
      (node (ref "U7") (pin "2") (pinfunction "IN_2") (pintype "passive"))
    )
    (net (code "26") (name "/M3_B") (class "Default")
      (node (ref "U1") (pin "41") (pinfunction "PB5_41") (pintype "bidirectional"))
      (node (ref "U8") (pin "2") (pinfunction "IN_2") (pintype "passive"))
    )
    (net (code "27") (name "/M3_HA") (class "Default")
      (node (ref "C21") (pin "2") (pinfunction "2_2") (pintype "passive"))
      (node (ref "D14") (pin "2") (pinfunction "K_2") (pintype "passive"))
      (node (ref "J3") (pin "1") (pinfunction "1_1") (pintype "passive"))
      (node (ref "Q10") (pin "3") (pinfunction "S_3") (pintype "input"))
      (node (ref "Q12") (pin "2") (pinfunction "D_2") (pintype "input"))
      (node (ref "R23") (pin "2") (pinfunction "2_2") (pintype "passive"))
      (node (ref "U7") (pin "6") (pinfunction "VS_6") (pintype "passive"))
    )
    (net (code "28") (name "/M3_HB") (class "Default")
      (node (ref "C22") (pin "2") (pinfunction "2_2") (pintype "passive"))
      (node (ref "D13") (pin "2") (pinfunction "K_2") (pintype "passive"))
      (node (ref "J3") (pin "2") (pinfunction "2_2") (pintype "passive"))
      (node (ref "Q11") (pin "2") (pinfunction "D_2") (pintype "input"))
      (node (ref "Q9") (pin "3") (pinfunction "S_3") (pintype "input"))
      (node (ref "R24") (pin "2") (pinfunction "2_2") (pintype "passive"))
      (node (ref "U8") (pin "6") (pinfunction "VS_6") (pintype "passive"))
    )
    (net (code "29") (name "/M4_A") (class "Default")
      (node (ref "U1") (pin "18") (pinfunction "PB0_18") (pintype "bidirectional"))
      (node (ref "U9") (pin "2") (pinfunction "IN_2") (pintype "passive"))
    )
    (net (code "30") (name "/M4_B") (class "Default")
      (node (ref "U1") (pin "19") (pinfunction "PB1_19") (pintype "bidirectional"))
      (node (ref "U10") (pin "2") (pinfunction "IN_2") (pintype "passive"))
    )
    (net (code "31") (name "/M4_HA") (class "Default")
      (node (ref "C25") (pin "2") (pinfunction "2_2") (pintype "passive"))
      (node (ref "D16") (pin "2") (pinfunction "K_2") (pintype "passive"))
      (node (ref "J4") (pin "1") (pinfunction "1_1") (pintype "passive"))
      (node (ref "Q14") (pin "3") (pinfunction "S_3") (pintype "input"))
      (node (ref "Q16") (pin "2") (pinfunction "D_2") (pintype "input"))
      (node (ref "R33") (pin "2") (pinfunction "2_2") (pintype "passive"))
      (node (ref "U9") (pin "6") (pinfunction "VS_6") (pintype "passive"))
    )
    (net (code "32") (name "/M4_HB") (class "Default")
      (node (ref "C26") (pin "2") (pinfunction "2_2") (pintype "passive"))
      (node (ref "D15") (pin "2") (pinfunction "K_2") (pintype "passive"))
      (node (ref "J4") (pin "2") (pinfunction "2_2") (pintype "passive"))
      (node (ref "Q13") (pin "3") (pinfunction "S_3") (pintype "input"))
      (node (ref "Q15") (pin "2") (pinfunction "D_2") (pintype "input"))
      (node (ref "R34") (pin "2") (pinfunction "2_2") (pintype "passive"))
      (node (ref "U10") (pin "6") (pinfunction "VS_6") (pintype "passive"))
    )
    (net (code "33") (name "/NRST") (class "Default")
      (node (ref "C39") (pin "2") (pinfunction "2_2") (pintype "passive"))
      (node (ref "R48") (pin "2") (pinfunction "2_2") (pintype "passive"))
      (node (ref "S1") (pin "1") (pinfunction "1_1") (pintype "passive"))
      (node (ref "U1") (pin "7") (pinfunction "NRST_7") (pintype "bidirectional"))
    )
    (net (code "34") (name "/PA12") (class "Default")
      (node (ref "U1") (pin "33") (pinfunction "PA12_33") (pintype "bidirectional+no_connect"))
    )
    (net (code "35") (name "/PA13") (class "Default")
      (node (ref "R45") (pin "1") (pinfunction "1_1") (pintype "passive"))
      (node (ref "U1") (pin "34") (pinfunction "PA13(SWDIO)_34") (pintype "bidirectional"))
    )
    (net (code "36") (name "/PA14") (class "Default")
      (node (ref "R46") (pin "1") (pinfunction "1_1") (pintype "passive"))
      (node (ref "U1") (pin "37") (pinfunction "PA14(SWCLK)_37") (pintype "bidirectional"))
    )
    (net (code "37") (name "/PA15") (class "Default")
      (node (ref "U1") (pin "38") (pinfunction "PA15_38") (pintype "bidirectional+no_connect"))
    )
    (net (code "38") (name "/PB2") (class "Default")
      (node (ref "U1") (pin "20") (pinfunction "PB2_20") (pintype "bidirectional+no_connect"))
    )
    (net (code "39") (name "/PB3") (class "Default")
      (node (ref "U1") (pin "39") (pinfunction "PB3_39") (pintype "bidirectional+no_connect"))
    )
    (net (code "40") (name "/PB6") (class "Default")
      (node (ref "P4") (pin "3") (pinfunction "3_3") (pintype "passive"))
      (node (ref "U1") (pin "42") (pinfunction "PB6_42") (pintype "bidirectional"))
    )
    (net (code "41") (name "/PB7") (class "Default")
      (node (ref "P4") (pin "2") (pinfunction "2_2") (pintype "passive"))
      (node (ref "U1") (pin "43") (pinfunction "PB7_43") (pintype "bidirectional"))
    )
    (net (code "42") (name "/PB8") (class "Default")
      (node (ref "P7") (pin "1") (pinfunction "1_1") (pintype "passive"))
      (node (ref "U1") (pin "45") (pinfunction "PB8_45") (pintype "bidirectional"))
    )
    (net (code "43") (name "/PB9") (class "Default")
      (node (ref "P7") (pin "3") (pinfunction "3_3") (pintype "passive"))
      (node (ref "U1") (pin "46") (pinfunction "PB9_46") (pintype "bidirectional"))
    )
    (net (code "44") (name "/PB10") (class "Default")
      (node (ref "P7") (pin "5") (pinfunction "5_5") (pintype "passive"))
      (node (ref "U1") (pin "21") (pinfunction "PB10_21") (pintype "bidirectional"))
    )
    (net (code "45") (name "/PB11") (class "Default")
      (node (ref "P7") (pin "7") (pinfunction "7_7") (pintype "passive"))
      (node (ref "U1") (pin "22") (pinfunction "PB11_22") (pintype "bidirectional"))
    )
    (net (code "46") (name "/PB12") (class "Default")
      (node (ref "P7") (pin "9") (pinfunction "9_9") (pintype "passive"))
      (node (ref "U1") (pin "25") (pinfunction "PB12_25") (pintype "bidirectional"))
    )
    (net (code "47") (name "/PB13") (class "Default")
      (node (ref "P7") (pin "11") (pinfunction "11_11") (pintype "passive"))
      (node (ref "U1") (pin "26") (pinfunction "PB13_26") (pintype "bidirectional"))
    )
    (net (code "48") (name "/PC14") (class "Default")
      (node (ref "U1") (pin "3") (pinfunction "PC14-OSC32_IN(PC14)_3") (pintype "bidirectional+no_connect"))
    )
    (net (code "49") (name "/PC15") (class "Default")
      (node (ref "U1") (pin "4") (pinfunction "PC15-OSC32_OUT(PC15)_4") (pintype "bidirectional+no_connect"))
    )
    (net (code "50") (name "/PF0") (class "Default")
      (node (ref "U1") (pin "5") (pinfunction "PF0-OSC_IN(PF0)_5") (pintype "bidirectional+no_connect"))
    )
    (net (code "51") (name "/PF1") (class "Default")
      (node (ref "U1") (pin "6") (pinfunction "PF1-OSC_OUT(PF1)_6") (pintype "bidirectional+no_connect"))
    )
    (net (code "52") (name "/PF6") (class "Default")
      (node (ref "U1") (pin "35") (pinfunction "PF6_35") (pintype "bidirectional+no_connect"))
    )
    (net (code "53") (name "/PF7") (class "Default")
      (node (ref "U1") (pin "36") (pinfunction "PF7_36") (pintype "bidirectional+no_connect"))
    )
    (net (code "54") (name "GND") (class "Default")
      (node (ref "C1") (pin "2") (pinfunction "2_2") (pintype "passive"))
      (node (ref "C10") (pin "2") (pinfunction "2_2") (pintype "passive"))
      (node (ref "C11") (pin "2") (pinfunction "2_2") (pintype "passive"))
      (node (ref "C12") (pin "2") (pinfunction "2_2") (pintype "passive"))
      (node (ref "C15") (pin "2") (pinfunction "2_2") (pintype "passive"))
      (node (ref "C16") (pin "2") (pinfunction "2_2") (pintype "passive"))
      (node (ref "C19") (pin "2") (pinfunction "2_2") (pintype "passive"))
      (node (ref "C2") (pin "2") (pinfunction "2_2") (pintype "passive"))
      (node (ref "C20") (pin "2") (pinfunction "2_2") (pintype "passive"))
      (node (ref "C23") (pin "2") (pinfunction "2_2") (pintype "passive"))
      (node (ref "C24") (pin "2") (pinfunction "2_2") (pintype "passive"))
      (node (ref "C27") (pin "2") (pinfunction "2_2") (pintype "passive"))
      (node (ref "C28") (pin "2") (pinfunction "2_2") (pintype "passive"))
      (node (ref "C3") (pin "2") (pinfunction "2_2") (pintype "passive"))
      (node (ref "C39") (pin "1") (pinfunction "1_1") (pintype "passive"))
      (node (ref "C4") (pin "2") (pinfunction "2_2") (pintype "passive"))
      (node (ref "C40") (pin "2") (pinfunction "2_2") (pintype "passive"))
      (node (ref "C41") (pin "2") (pinfunction "2_2") (pintype "passive"))
      (node (ref "C42") (pin "2") (pinfunction "2_2") (pintype "passive"))
      (node (ref "C43") (pin "2") (pinfunction "2_2") (pintype "passive"))
      (node (ref "C5") (pin "2") (pinfunction "2_2") (pintype "passive"))
      (node (ref "C6") (pin "2") (pinfunction "2_2") (pintype "passive"))
      (node (ref "C7") (pin "2") (pinfunction "2_2") (pintype "passive"))
      (node (ref "C8") (pin "2") (pinfunction "2_2") (pintype "passive"))
      (node (ref "C9") (pin "2") (pinfunction "2_2") (pintype "passive"))
      (node (ref "DS2") (pin "2") (pinfunction "K_2") (pintype "passive"))
      (node (ref "DS3") (pin "2") (pinfunction "K_2") (pintype "passive"))
      (node (ref "DS4") (pin "2") (pinfunction "K_2") (pintype "passive"))
      (node (ref "J5") (pin "2") (pinfunction "2_2") (pintype "passive"))
      (node (ref "L2") (pin "2") (pinfunction "2_2") (pintype "passive"))
      (node (ref "P1") (pin "1") (pinfunction "1_1") (pintype "passive"))
      (node (ref "P1") (pin "3") (pinfunction "3_3") (pintype "passive"))
      (node (ref "P3") (pin "5") (pinfunction "5_5") (pintype "passive"))
      (node (ref "P4") (pin "4") (pinfunction "4_4") (pintype "passive"))
      (node (ref "P5") (pin "4") (pinfunction "4_4") (pintype "passive"))
      (node (ref "P6") (pin "1") (pinfunction "1_1") (pintype "passive"))
      (node (ref "P7") (pin "10") (pinfunction "10_10") (pintype "passive"))
      (node (ref "P7") (pin "12") (pinfunction "12_12") (pintype "passive"))
      (node (ref "P7") (pin "2") (pinfunction "2_2") (pintype "passive"))
      (node (ref "P7") (pin "4") (pinfunction "4_4") (pintype "passive"))
      (node (ref "P7") (pin "6") (pinfunction "6_6") (pintype "passive"))
      (node (ref "P7") (pin "8") (pinfunction "8_8") (pintype "passive"))
      (node (ref "R10") (pin "1") (pinfunction "1_1") (pintype "passive"))
      (node (ref "R17") (pin "1") (pinfunction "1_1") (pintype "passive"))
      (node (ref "R20") (pin "1") (pinfunction "1_1") (pintype "passive"))
      (node (ref "R27") (pin "1") (pinfunction "1_1") (pintype "passive"))
      (node (ref "R30") (pin "1") (pinfunction "1_1") (pintype "passive"))
      (node (ref "R37") (pin "1") (pinfunction "1_1") (pintype "passive"))
      (node (ref "R40") (pin "1") (pinfunction "1_1") (pintype "passive"))
      (node (ref "R43") (pin "2") (pinfunction "2_2") (pintype "passive"))
      (node (ref "R44") (pin "2") (pinfunction "2_2") (pintype "passive"))
      (node (ref "R7") (pin "1") (pinfunction "1_1") (pintype "passive"))
      (node (ref "S1") (pin "2") (pinfunction "2_2") (pintype "passive"))
      (node (ref "U") (pin "4") (pinfunction "COM_4") (pintype "passive"))
      (node (ref "U1") (pin "23") (pinfunction "VSS_23") (pintype "power_in"))
      (node (ref "U1") (pin "47") (pinfunction "VSS_47") (pintype "power_in"))
      (node (ref "U1") (pin "8") (pinfunction "VSSA_8") (pintype "power_in"))
      (node (ref "U10") (pin "4") (pinfunction "COM_4") (pintype "passive"))
      (node (ref "U2") (pin "1") (pinfunction "GND_1") (pintype "passive"))
      (node (ref "U3") (pin "2") (pinfunction "2_2") (pintype "passive"))
      (node (ref "U4") (pin "4") (pinfunction "COM_4") (pintype "passive"))
      (node (ref "U5") (pin "4") (pinfunction "COM_4") (pintype "passive"))
      (node (ref "U6") (pin "4") (pinfunction "COM_4") (pintype "passive"))
      (node (ref "U7") (pin "4") (pinfunction "COM_4") (pintype "passive"))
      (node (ref "U8") (pin "4") (pinfunction "COM_4") (pintype "passive"))
      (node (ref "U9") (pin "4") (pinfunction "COM_4") (pintype "passive"))
    )
    (net (code "55") (name "GND_M") (class "Default")
      (node (ref "C29") (pin "2") (pinfunction "2_2") (pintype "passive"))
      (node (ref "C30") (pin "2") (pinfunction "2_2") (pintype "passive"))
      (node (ref "C31") (pin "2") (pinfunction "2_2") (pintype "passive"))
      (node (ref "C32") (pin "2") (pinfunction "2_2") (pintype "passive"))
      (node (ref "C33") (pin "2") (pinfunction "2_2") (pintype "passive"))
      (node (ref "C34") (pin "2") (pinfunction "2_2") (pintype "passive"))
      (node (ref "C35") (pin "2") (pinfunction "2_2") (pintype "passive"))
      (node (ref "C36") (pin "2") (pinfunction "2_2") (pintype "passive"))
      (node (ref "C37") (pin "2") (pinfunction "2_2") (pintype "passive"))
      (node (ref "C38") (pin "2") (pinfunction "2_2") (pintype "passive"))
      (node (ref "D10") (pin "1") (pinfunction "A_1") (pintype "passive"))
      (node (ref "D11") (pin "1") (pinfunction "A_1") (pintype "passive"))
      (node (ref "D12") (pin "1") (pinfunction "A_1") (pintype "passive"))
      (node (ref "D13") (pin "1") (pinfunction "A_1") (pintype "passive"))
      (node (ref "D14") (pin "1") (pinfunction "A_1") (pintype "passive"))
      (node (ref "D15") (pin "1") (pinfunction "A_1") (pintype "passive"))
      (node (ref "D16") (pin "1") (pinfunction "A_1") (pintype "passive"))
      (node (ref "D9") (pin "1") (pinfunction "A_1") (pintype "passive"))
      (node (ref "DS1") (pin "2") (pinfunction "K_2") (pintype "passive"))
      (node (ref "J6") (pin "1") (pinfunction "1_1") (pintype "passive"))
      (node (ref "L2") (pin "1") (pinfunction "1_1") (pintype "passive"))
      (node (ref "P2") (pin "1") (pinfunction "1_1") (pintype "passive"))
      (node (ref "P2") (pin "3") (pinfunction "3_3") (pintype "passive"))
      (node (ref "P2") (pin "5") (pinfunction "5_5") (pintype "passive"))
      (node (ref "P2") (pin "7") (pinfunction "7_7") (pintype "passive"))
      (node (ref "R18") (pin "2") (pinfunction "2_2") (pintype "passive"))
      (node (ref "R19") (pin "1") (pinfunction "1_1") (pintype "passive"))
      (node (ref "R28") (pin "2") (pinfunction "2_2") (pintype "passive"))
      (node (ref "R29") (pin "1") (pinfunction "1_1") (pintype "passive"))
      (node (ref "R38") (pin "2") (pinfunction "2_2") (pintype "passive"))
      (node (ref "R39") (pin "1") (pinfunction "1_1") (pintype "passive"))
      (node (ref "R8") (pin "2") (pinfunction "2_2") (pintype "passive"))
      (node (ref "R9") (pin "1") (pinfunction "1_1") (pintype "passive"))
    )
    (net (code "56") (name "Net-(C29-Pad1)") (class "Default")
      (node (ref "C29") (pin "1") (pinfunction "1_1") (pintype "passive"))
      (node (ref "J6") (pin "2") (pinfunction "2_2") (pintype "passive"))
      (node (ref "L1") (pin "1") (pinfunction "1_1") (pintype "passive"))
      (node (ref "P2") (pin "2") (pinfunction "2_2") (pintype "passive"))
      (node (ref "P2") (pin "4") (pinfunction "4_4") (pintype "passive"))
      (node (ref "P2") (pin "6") (pinfunction "6_6") (pintype "passive"))
      (node (ref "P2") (pin "8") (pinfunction "8_8") (pintype "passive"))
      (node (ref "R41") (pin "1") (pinfunction "1_1") (pintype "passive"))
    )
    (net (code "57") (name "Net-(D1-K)") (class "Default")
      (node (ref "C13") (pin "1") (pinfunction "1_1") (pintype "passive"))
      (node (ref "D1") (pin "2") (pinfunction "K_2") (pintype "passive"))
      (node (ref "U") (pin "8") (pinfunction "VB_8") (pintype "passive"))
    )
    (net (code "58") (name "Net-(D2-K)") (class "Default")
      (node (ref "C14") (pin "1") (pinfunction "1_1") (pintype "passive"))
      (node (ref "D2") (pin "2") (pinfunction "K_2") (pintype "passive"))
      (node (ref "U4") (pin "8") (pinfunction "VB_8") (pintype "passive"))
    )
    (net (code "59") (name "Net-(D3-K)") (class "Default")
      (node (ref "C17") (pin "1") (pinfunction "1_1") (pintype "passive"))
      (node (ref "D3") (pin "2") (pinfunction "K_2") (pintype "passive"))
      (node (ref "U5") (pin "8") (pinfunction "VB_8") (pintype "passive"))
    )
    (net (code "60") (name "Net-(D4-K)") (class "Default")
      (node (ref "C18") (pin "1") (pinfunction "1_1") (pintype "passive"))
      (node (ref "D4") (pin "2") (pinfunction "K_2") (pintype "passive"))
      (node (ref "U6") (pin "8") (pinfunction "VB_8") (pintype "passive"))
    )
    (net (code "61") (name "Net-(D5-K)") (class "Default")
      (node (ref "C21") (pin "1") (pinfunction "1_1") (pintype "passive"))
      (node (ref "D5") (pin "2") (pinfunction "K_2") (pintype "passive"))
      (node (ref "U7") (pin "8") (pinfunction "VB_8") (pintype "passive"))
    )
    (net (code "62") (name "Net-(D6-K)") (class "Default")
      (node (ref "C22") (pin "1") (pinfunction "1_1") (pintype "passive"))
      (node (ref "D6") (pin "2") (pinfunction "K_2") (pintype "passive"))
      (node (ref "U8") (pin "8") (pinfunction "VB_8") (pintype "passive"))
    )
    (net (code "63") (name "Net-(D7-K)") (class "Default")
      (node (ref "C25") (pin "1") (pinfunction "1_1") (pintype "passive"))
      (node (ref "D7") (pin "2") (pinfunction "K_2") (pintype "passive"))
      (node (ref "U9") (pin "8") (pinfunction "VB_8") (pintype "passive"))
    )
    (net (code "64") (name "Net-(D8-K)") (class "Default")
      (node (ref "C26") (pin "1") (pinfunction "1_1") (pintype "passive"))
      (node (ref "D8") (pin "2") (pinfunction "K_2") (pintype "passive"))
      (node (ref "U10") (pin "8") (pinfunction "VB_8") (pintype "passive"))
    )
    (net (code "65") (name "Net-(DS1-A)") (class "Default")
      (node (ref "DS1") (pin "1") (pinfunction "A_1") (pintype "passive"))
      (node (ref "R49") (pin "1") (pinfunction "1_1") (pintype "passive"))
    )
    (net (code "66") (name "Net-(DS2-A)") (class "Default")
      (node (ref "DS2") (pin "1") (pinfunction "A_1") (pintype "passive"))
      (node (ref "R50") (pin "1") (pinfunction "1_1") (pintype "passive"))
    )
    (net (code "67") (name "Net-(DS3-A)") (class "Default")
      (node (ref "DS3") (pin "1") (pinfunction "A_1") (pintype "passive"))
      (node (ref "R51") (pin "1") (pinfunction "1_1") (pintype "passive"))
    )
    (net (code "68") (name "Net-(DS4-A)") (class "Default")
      (node (ref "DS4") (pin "1") (pinfunction "A_1") (pintype "passive"))
      (node (ref "R52") (pin "1") (pinfunction "1_1") (pintype "passive"))
    )
    (net (code "69") (name "Net-(P5-Pad2)") (class "Default")
      (node (ref "P5") (pin "2") (pinfunction "2_2") (pintype "passive"))
      (node (ref "R45") (pin "2") (pinfunction "2_2") (pintype "passive"))
    )
    (net (code "70") (name "Net-(P5-Pad3)") (class "Default")
      (node (ref "P5") (pin "3") (pinfunction "3_3") (pintype "passive"))
      (node (ref "R46") (pin "2") (pinfunction "2_2") (pintype "passive"))
    )
    (net (code "71") (name "Net-(P6-Pad2)") (class "Default")
      (node (ref "P6") (pin "2") (pinfunction "2_2") (pintype "passive"))
      (node (ref "R47") (pin "1") (pinfunction "1_1") (pintype "passive"))
    )
    (net (code "72") (name "Net-(Q1-G)") (class "Default")
      (node (ref "Q1") (pin "1") (pinfunction "G_1") (pintype "input"))
      (node (ref "R1") (pin "2") (pinfunction "2_2") (pintype "passive"))
      (node (ref "R4") (pin "1") (pinfunction "1_1") (pintype "passive"))
    )
    (net (code "73") (name "Net-(Q2-G)") (class "Default")
      (node (ref "Q2") (pin "1") (pinfunction "G_1") (pintype "input"))
      (node (ref "R2") (pin "2") (pinfunction "2_2") (pintype "passive"))
      (node (ref "R3") (pin "1") (pinfunction "1_1") (pintype "passive"))
    )
    (net (code "74") (name "Net-(Q3-G)") (class "Default")
      (node (ref "Q3") (pin "1") (pinfunction "G_1") (pintype "input"))
      (node (ref "R5") (pin "2") (pinfunction "2_2") (pintype "passive"))
      (node (ref "R7") (pin "2") (pinfunction "2_2") (pintype "passive"))
    )
    (net (code "75") (name "Net-(Q4-G)") (class "Default")
      (node (ref "Q4") (pin "1") (pinfunction "G_1") (pintype "input"))
      (node (ref "R10") (pin "2") (pinfunction "2_2") (pintype "passive"))
      (node (ref "R6") (pin "2") (pinfunction "2_2") (pintype "passive"))
    )
    (net (code "76") (name "Net-(Q5-G)") (class "Default")
      (node (ref "Q5") (pin "1") (pinfunction "G_1") (pintype "input"))
      (node (ref "R11") (pin "2") (pinfunction "2_2") (pintype "passive"))
      (node (ref "R14") (pin "1") (pinfunction "1_1") (pintype "passive"))
    )
    (net (code "77") (name "Net-(Q6-G)") (class "Default")
      (node (ref "Q6") (pin "1") (pinfunction "G_1") (pintype "input"))
      (node (ref "R12") (pin "2") (pinfunction "2_2") (pintype "passive"))
      (node (ref "R13") (pin "1") (pinfunction "1_1") (pintype "passive"))
    )
    (net (code "78") (name "Net-(Q7-G)") (class "Default")
      (node (ref "Q7") (pin "1") (pinfunction "G_1") (pintype "input"))
      (node (ref "R15") (pin "2") (pinfunction "2_2") (pintype "passive"))
      (node (ref "R17") (pin "2") (pinfunction "2_2") (pintype "passive"))
    )
    (net (code "79") (name "Net-(Q8-G)") (class "Default")
      (node (ref "Q8") (pin "1") (pinfunction "G_1") (pintype "input"))
      (node (ref "R16") (pin "2") (pinfunction "2_2") (pintype "passive"))
      (node (ref "R20") (pin "2") (pinfunction "2_2") (pintype "passive"))
    )
    (net (code "80") (name "Net-(Q9-G)") (class "Default")
      (node (ref "Q9") (pin "1") (pinfunction "G_1") (pintype "input"))
      (node (ref "R21") (pin "2") (pinfunction "2_2") (pintype "passive"))
      (node (ref "R24") (pin "1") (pinfunction "1_1") (pintype "passive"))
    )
    (net (code "81") (name "Net-(Q10-G)") (class "Default")
      (node (ref "Q10") (pin "1") (pinfunction "G_1") (pintype "input"))
      (node (ref "R22") (pin "2") (pinfunction "2_2") (pintype "passive"))
      (node (ref "R23") (pin "1") (pinfunction "1_1") (pintype "passive"))
    )
    (net (code "82") (name "Net-(Q11-G)") (class "Default")
      (node (ref "Q11") (pin "1") (pinfunction "G_1") (pintype "input"))
      (node (ref "R25") (pin "2") (pinfunction "2_2") (pintype "passive"))
      (node (ref "R27") (pin "2") (pinfunction "2_2") (pintype "passive"))
    )
    (net (code "83") (name "Net-(Q12-G)") (class "Default")
      (node (ref "Q12") (pin "1") (pinfunction "G_1") (pintype "input"))
      (node (ref "R26") (pin "2") (pinfunction "2_2") (pintype "passive"))
      (node (ref "R30") (pin "2") (pinfunction "2_2") (pintype "passive"))
    )
    (net (code "84") (name "Net-(Q13-G)") (class "Default")
      (node (ref "Q13") (pin "1") (pinfunction "G_1") (pintype "input"))
      (node (ref "R31") (pin "2") (pinfunction "2_2") (pintype "passive"))
      (node (ref "R34") (pin "1") (pinfunction "1_1") (pintype "passive"))
    )
    (net (code "85") (name "Net-(Q14-G)") (class "Default")
      (node (ref "Q14") (pin "1") (pinfunction "G_1") (pintype "input"))
      (node (ref "R32") (pin "2") (pinfunction "2_2") (pintype "passive"))
      (node (ref "R33") (pin "1") (pinfunction "1_1") (pintype "passive"))
    )
    (net (code "86") (name "Net-(Q15-G)") (class "Default")
      (node (ref "Q15") (pin "1") (pinfunction "G_1") (pintype "input"))
      (node (ref "R35") (pin "2") (pinfunction "2_2") (pintype "passive"))
      (node (ref "R37") (pin "2") (pinfunction "2_2") (pintype "passive"))
    )
    (net (code "87") (name "Net-(Q16-G)") (class "Default")
      (node (ref "Q16") (pin "1") (pinfunction "G_1") (pintype "input"))
      (node (ref "R36") (pin "2") (pinfunction "2_2") (pintype "passive"))
      (node (ref "R40") (pin "2") (pinfunction "2_2") (pintype "passive"))
    )
    (net (code "88") (name "Net-(U-HO)") (class "Default")
      (node (ref "R2") (pin "1") (pinfunction "1_1") (pintype "passive"))
      (node (ref "U") (pin "7") (pinfunction "HO_7") (pintype "passive"))
    )
    (net (code "89") (name "Net-(U-LO)") (class "Default")
      (node (ref "R6") (pin "1") (pinfunction "1_1") (pintype "passive"))
      (node (ref "U") (pin "5") (pinfunction "LO_5") (pintype "passive"))
    )
    (net (code "90") (name "Net-(U4-HO)") (class "Default")
      (node (ref "R1") (pin "1") (pinfunction "1_1") (pintype "passive"))
      (node (ref "U4") (pin "7") (pinfunction "HO_7") (pintype "passive"))
    )
    (net (code "91") (name "Net-(U4-LO)") (class "Default")
      (node (ref "R5") (pin "1") (pinfunction "1_1") (pintype "passive"))
      (node (ref "U4") (pin "5") (pinfunction "LO_5") (pintype "passive"))
    )
    (net (code "92") (name "Net-(U5-HO)") (class "Default")
      (node (ref "R12") (pin "1") (pinfunction "1_1") (pintype "passive"))
      (node (ref "U5") (pin "7") (pinfunction "HO_7") (pintype "passive"))
    )
    (net (code "93") (name "Net-(U5-LO)") (class "Default")
      (node (ref "R16") (pin "1") (pinfunction "1_1") (pintype "passive"))
      (node (ref "U5") (pin "5") (pinfunction "LO_5") (pintype "passive"))
    )
    (net (code "94") (name "Net-(U6-HO)") (class "Default")
      (node (ref "R11") (pin "1") (pinfunction "1_1") (pintype "passive"))
      (node (ref "U6") (pin "7") (pinfunction "HO_7") (pintype "passive"))
    )
    (net (code "95") (name "Net-(U6-LO)") (class "Default")
      (node (ref "R15") (pin "1") (pinfunction "1_1") (pintype "passive"))
      (node (ref "U6") (pin "5") (pinfunction "LO_5") (pintype "passive"))
    )
    (net (code "96") (name "Net-(U7-HO)") (class "Default")
      (node (ref "R22") (pin "1") (pinfunction "1_1") (pintype "passive"))
      (node (ref "U7") (pin "7") (pinfunction "HO_7") (pintype "passive"))
    )
    (net (code "97") (name "Net-(U7-LO)") (class "Default")
      (node (ref "R26") (pin "1") (pinfunction "1_1") (pintype "passive"))
      (node (ref "U7") (pin "5") (pinfunction "LO_5") (pintype "passive"))
    )
    (net (code "98") (name "Net-(U8-HO)") (class "Default")
      (node (ref "R21") (pin "1") (pinfunction "1_1") (pintype "passive"))
      (node (ref "U8") (pin "7") (pinfunction "HO_7") (pintype "passive"))
    )
    (net (code "99") (name "Net-(U8-LO)") (class "Default")
      (node (ref "R25") (pin "1") (pinfunction "1_1") (pintype "passive"))
      (node (ref "U8") (pin "5") (pinfunction "LO_5") (pintype "passive"))
    )
    (net (code "100") (name "Net-(U9-HO)") (class "Default")
      (node (ref "R32") (pin "1") (pinfunction "1_1") (pintype "passive"))
      (node (ref "U9") (pin "7") (pinfunction "HO_7") (pintype "passive"))
    )
    (net (code "101") (name "Net-(U9-LO)") (class "Default")
      (node (ref "R36") (pin "1") (pinfunction "1_1") (pintype "passive"))
      (node (ref "U9") (pin "5") (pinfunction "LO_5") (pintype "passive"))
    )
    (net (code "102") (name "Net-(U10-HO)") (class "Default")
      (node (ref "R31") (pin "1") (pinfunction "1_1") (pintype "passive"))
      (node (ref "U10") (pin "7") (pinfunction "HO_7") (pintype "passive"))
    )
    (net (code "103") (name "Net-(U10-LO)") (class "Default")
      (node (ref "R35") (pin "1") (pinfunction "1_1") (pintype "passive"))
      (node (ref "U10") (pin "5") (pinfunction "LO_5") (pintype "passive"))
    )
    (net (code "104") (name "VCC_3V3") (class "Default")
      (node (ref "C10") (pin "1") (pinfunction "1_1") (pintype "passive"))
      (node (ref "C11") (pin "1") (pinfunction "1_1") (pintype "passive"))
      (node (ref "C12") (pin "1") (pinfunction "1_1") (pintype "passive"))
      (node (ref "C7") (pin "1") (pinfunction "1_1") (pintype "passive"))
      (node (ref "C8") (pin "1") (pinfunction "1_1") (pintype "passive"))
      (node (ref "C9") (pin "1") (pinfunction "1_1") (pintype "passive"))
      (node (ref "P5") (pin "1") (pinfunction "1_1") (pintype "passive"))
      (node (ref "P6") (pin "3") (pinfunction "3_3") (pintype "passive"))
      (node (ref "R48") (pin "1") (pinfunction "1_1") (pintype "passive"))
      (node (ref "R51") (pin "2") (pinfunction "2_2") (pintype "passive"))
      (node (ref "U1") (pin "1") (pinfunction "VDD_1") (pintype "power_in"))
      (node (ref "U1") (pin "24") (pinfunction "VDD_24") (pintype "power_in"))
      (node (ref "U1") (pin "48") (pinfunction "VDD_48") (pintype "power_in"))
      (node (ref "U1") (pin "9") (pinfunction "VDDA_9") (pintype "power_in"))
      (node (ref "U2") (pin "2") (pinfunction "OUT_2") (pintype "passive"))
      (node (ref "U2") (pin "4") (pinfunction "OUT_4") (pintype "passive"))
    )
    (net (code "105") (name "VCC_5V") (class "Default")
      (node (ref "C2") (pin "1") (pinfunction "1_1") (pintype "passive"))
      (node (ref "C4") (pin "1") (pinfunction "1_1") (pintype "passive"))
      (node (ref "C5") (pin "1") (pinfunction "1_1") (pintype "passive"))
      (node (ref "C6") (pin "1") (pinfunction "1_1") (pintype "passive"))
      (node (ref "P4") (pin "1") (pinfunction "1_1") (pintype "passive"))
      (node (ref "U2") (pin "3") (pinfunction "IN_3") (pintype "passive"))
      (node (ref "U3") (pin "3") (pinfunction "3_3") (pintype "passive"))
    )
    (net (code "106") (name "VCC_12V") (class "Default")
      (node (ref "C1") (pin "1") (pinfunction "1_1") (pintype "passive"))
      (node (ref "C15") (pin "1") (pinfunction "1_1") (pintype "passive"))
      (node (ref "C16") (pin "1") (pinfunction "1_1") (pintype "passive"))
      (node (ref "C19") (pin "1") (pinfunction "1_1") (pintype "passive"))
      (node (ref "C20") (pin "1") (pinfunction "1_1") (pintype "passive"))
      (node (ref "C23") (pin "1") (pinfunction "1_1") (pintype "passive"))
      (node (ref "C24") (pin "1") (pinfunction "1_1") (pintype "passive"))
      (node (ref "C27") (pin "1") (pinfunction "1_1") (pintype "passive"))
      (node (ref "C28") (pin "1") (pinfunction "1_1") (pintype "passive"))
      (node (ref "C3") (pin "1") (pinfunction "1_1") (pintype "passive"))
      (node (ref "D1") (pin "1") (pinfunction "A_1") (pintype "passive"))
      (node (ref "D2") (pin "1") (pinfunction "A_1") (pintype "passive"))
      (node (ref "D3") (pin "1") (pinfunction "A_1") (pintype "passive"))
      (node (ref "D4") (pin "1") (pinfunction "A_1") (pintype "passive"))
      (node (ref "D5") (pin "1") (pinfunction "A_1") (pintype "passive"))
      (node (ref "D6") (pin "1") (pinfunction "A_1") (pintype "passive"))
      (node (ref "D7") (pin "1") (pinfunction "A_1") (pintype "passive"))
      (node (ref "D8") (pin "1") (pinfunction "A_1") (pintype "passive"))
      (node (ref "J5") (pin "1") (pinfunction "1_1") (pintype "passive"))
      (node (ref "P1") (pin "2") (pinfunction "2_2") (pintype "passive"))
      (node (ref "P1") (pin "4") (pinfunction "4_4") (pintype "passive"))
      (node (ref "R42") (pin "1") (pinfunction "1_1") (pintype "passive"))
      (node (ref "R50") (pin "2") (pinfunction "2_2") (pintype "passive"))
      (node (ref "U") (pin "1") (pinfunction "VCC_1") (pintype "passive"))
      (node (ref "U") (pin "3") (pinfunction "SD_3") (pintype "passive"))
      (node (ref "U10") (pin "1") (pinfunction "VCC_1") (pintype "passive"))
      (node (ref "U10") (pin "3") (pinfunction "SD_3") (pintype "passive"))
      (node (ref "U3") (pin "1") (pinfunction "1_1") (pintype "passive"))
      (node (ref "U4") (pin "1") (pinfunction "VCC_1") (pintype "passive"))
      (node (ref "U4") (pin "3") (pinfunction "SD_3") (pintype "passive"))
      (node (ref "U5") (pin "1") (pinfunction "VCC_1") (pintype "passive"))
      (node (ref "U5") (pin "3") (pinfunction "SD_3") (pintype "passive"))
      (node (ref "U6") (pin "1") (pinfunction "VCC_1") (pintype "passive"))
      (node (ref "U6") (pin "3") (pinfunction "SD_3") (pintype "passive"))
      (node (ref "U7") (pin "1") (pinfunction "VCC_1") (pintype "passive"))
      (node (ref "U7") (pin "3") (pinfunction "SD_3") (pintype "passive"))
      (node (ref "U8") (pin "1") (pinfunction "VCC_1") (pintype "passive"))
      (node (ref "U8") (pin "3") (pinfunction "SD_3") (pintype "passive"))
      (node (ref "U9") (pin "1") (pinfunction "VCC_1") (pintype "passive"))
      (node (ref "U9") (pin "3") (pinfunction "SD_3") (pintype "passive"))
    )
    (net (code "107") (name "VCC_M") (class "Default")
      (node (ref "C30") (pin "1") (pinfunction "1_1") (pintype "passive"))
      (node (ref "C31") (pin "1") (pinfunction "1_1") (pintype "passive"))
      (node (ref "C32") (pin "1") (pinfunction "1_1") (pintype "passive"))
      (node (ref "C33") (pin "1") (pinfunction "1_1") (pintype "passive"))
      (node (ref "C34") (pin "1") (pinfunction "1_1") (pintype "passive"))
      (node (ref "C35") (pin "1") (pinfunction "1_1") (pintype "passive"))
      (node (ref "C36") (pin "1") (pinfunction "1_1") (pintype "passive"))
      (node (ref "C37") (pin "1") (pinfunction "1_1") (pintype "passive"))
      (node (ref "C38") (pin "1") (pinfunction "1_1") (pintype "passive"))
      (node (ref "L1") (pin "2") (pinfunction "2_2") (pintype "passive"))
      (node (ref "Q1") (pin "2") (pinfunction "D_2") (pintype "input"))
      (node (ref "Q10") (pin "2") (pinfunction "D_2") (pintype "input"))
      (node (ref "Q13") (pin "2") (pinfunction "D_2") (pintype "input"))
      (node (ref "Q14") (pin "2") (pinfunction "D_2") (pintype "input"))
      (node (ref "Q2") (pin "2") (pinfunction "D_2") (pintype "input"))
      (node (ref "Q5") (pin "2") (pinfunction "D_2") (pintype "input"))
      (node (ref "Q6") (pin "2") (pinfunction "D_2") (pintype "input"))
      (node (ref "Q9") (pin "2") (pinfunction "D_2") (pintype "input"))
      (node (ref "R49") (pin "2") (pinfunction "2_2") (pintype "passive"))
    )
  )
)
